# pfe-final.net
KiCad netlist of a schematic drawn in Altium Designer
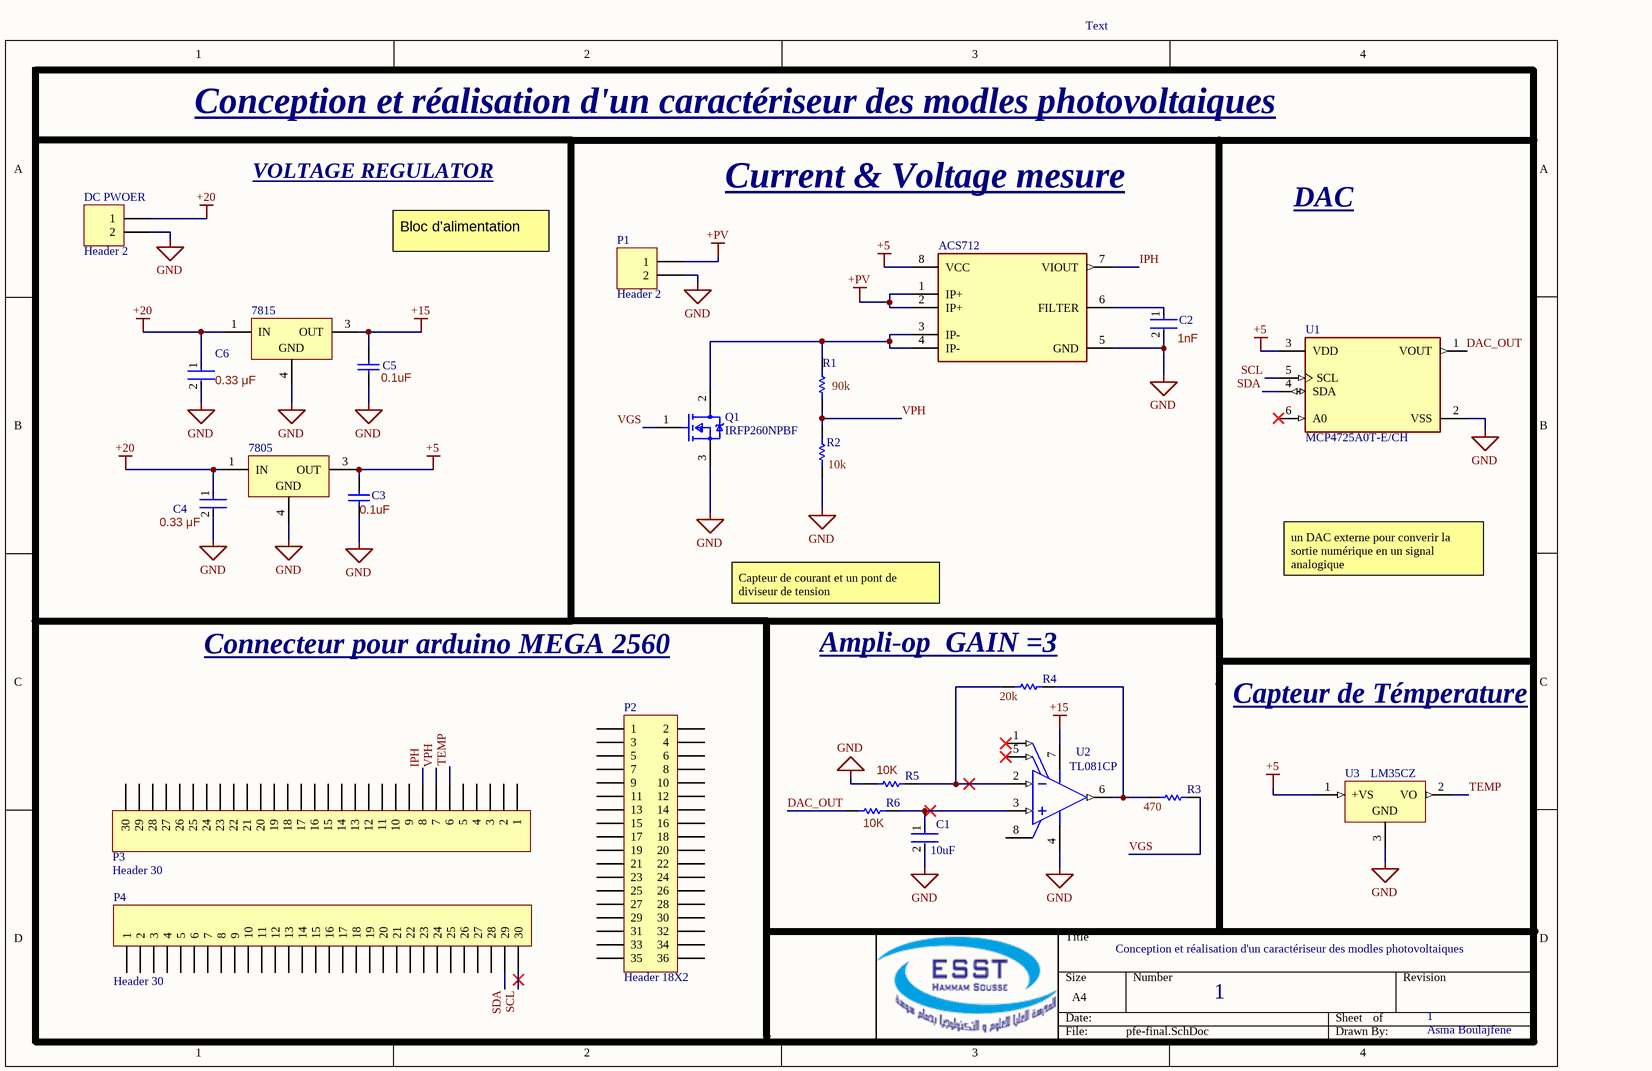
[diagram p0: pfe-final.SchDoc]

(export (version "E")
  (design (tool "Eeschema 10.0.6"))
  (components
    (comp (ref "7805")
      (value "L7805CD2T-TR")
      (footprint "TO-263_M")
      (description "Positive Voltage Regulator, 3-Pin D2PAK, Tape and Reel")
      (libsource (lib "Altium Content Vault") (part "PM-REG-L4940-SOT3"))
    )
    (comp (ref "7815")
      (value "L7815CD2T-TR")
      (footprint "TO-263_N")
      (description "Positive Voltage Regulator, 3-Pin D2PAK, Tape and Reel")
      (libsource (lib "Altium Content Vault") (part "PM-REG-L4940-SOT3"))
    )
    (comp (ref "ACS712")
      (value "ACS712ELCTR-30A-T")
      (footprint "FP-LC-8-IPC_C")
      (description "SENSOR CURRENT HALL 30A AC/DC")
      (libsource (lib "Altium Content Vault") (part "a0faa98973ef06dd62ff869f1199b2d"))
    )
    (comp (ref "C1")
      (value "10uF")
      (footprint "FP-C0805C-DG-MFG")
      (description "CAP CER 10UF 10V X5R 0805")
      (fields (field (name "TOLERANCE") "10%") (field (name "MANUFACTURER PART NUMBER") "C0805C106K8PACTU"))
      (libsource (lib "Altium Content Vault") (part "11868f565c42a9108669ba33697ecf6"))
    )
    (comp (ref "C2")
      (value "1nF")
      (footprint "FP-C0805C-DN-MFG")
      (description "CAP CER 1000PF 100V C0G/NP0 0805")
      (fields (field (name "MANUFACTURER") "KEMET") (field (name "TOLERANCE") "0.05"))
      (libsource (lib "Altium Content Vault") (part "b4654b650e69147ec39a6b967a45e02"))
    )
    (comp (ref "C3")
      (value "GRM21BR71H104KA01L")
      (footprint "CAPC2013X135X45ML10T25")
      (description "Chip Capacitor, 0.1 uF, +/- 10%, 50 V, -55 to 125 degC, 0805 (2012 Metric), RoHS, Tape and Reel")
      (fields
        (field (name "VOLTAGE") "50V")
        (field (name "CAPACITANCE") "0.1uF")
        (field (name "TOLERANCE") "10%")
      )
      (libsource (lib "Altium Content Vault") (part "CAP-NP-2"))
    )
    (comp (ref "C4")
      (value "0.33 μF")
      (footprint "FP-C0805C-DN-MFG")
      (description "CAP CER 0.33UF 50V X7R 0805")
      (fields
        (field (name "MANUFACTURER PART NUMBER") "C0805C334K5RACTU")
        (field (name "MANUFACTURER") "KEMET")
      )
      (libsource (lib "Altium Content Vault") (part "b4654b650e69147ec39a6b967a45e02"))
    )
    (comp (ref "C5")
      (value "GRM21BR71H104KA01L")
      (footprint "CAPC2013X135X45ML10T25")
      (description "Chip Capacitor, 0.1 uF, +/- 10%, 50 V, -55 to 125 degC, 0805 (2012 Metric), RoHS, Tape and Reel")
      (fields
        (field (name "VOLTAGE") "50V")
        (field (name "CAPACITANCE") "0.1uF")
        (field (name "TOLERANCE") "10%")
      )
      (libsource (lib "Altium Content Vault") (part "CAP-NP-2"))
    )
    (comp (ref "C6")
      (value "0.33 μF")
      (footprint "FP-C0805C-DN-MFG")
      (description "CAP CER 0.33UF 50V X7R 0805")
      (fields
        (field (name "MANUFACTURER PART NUMBER") "C0805C334K5RACTU")
        (field (name "MANUFACTURER") "KEMET")
      )
      (libsource (lib "Altium Content Vault") (part "b4654b650e69147ec39a6b967a45e02"))
    )
    (comp (ref "DC PWOER")
      (value "Header 2")
      (footprint "HDR1X2")
      (description "Header, 2-Pin")
      (fields (field (name "PUBLISHER") "Altium Limited"))
      (libsource (lib "Miscellaneous Connectors") (part "Header 2"))
    )
    (comp (ref "P1")
      (value "Header 2")
      (footprint "HDR1X2")
      (description "Header, 2-Pin")
      (fields (field (name "PUBLISHER") "Altium Limited"))
      (libsource (lib "Miscellaneous Connectors") (part "Header 2"))
    )
    (comp (ref "P2")
      (value "Header 18X2")
      (footprint "HDR2X18")
      (description "Header, 18-Pin, Dual row")
      (fields (field (name "PUBLISHER") "Altium Limited"))
      (libsource (lib "Miscellaneous Connectors") (part "Header 18X2"))
    )
    (comp (ref "P3")
      (value "Header 30")
      (footprint "HDR1X30")
      (description "Header, 30-Pin")
      (fields (field (name "PUBLISHER") "Altium Limited"))
      (libsource (lib "Miscellaneous Connectors") (part "Header 30"))
    )
    (comp (ref "P4")
      (value "Header 30")
      (footprint "HDR1X30")
      (description "Header, 30-Pin")
      (fields (field (name "PUBLISHER") "Altium Limited"))
      (libsource (lib "") (part "Header 30_1"))
    )
    (comp (ref "Q1")
      (value "IRFP260NPBF")
      (footprint "FP-PG-TO247-3-MFG")
      (description "MOSFET N-CH 200V 50A TO247AC")
      (libsource (lib "Altium Content Vault") (part "b09f7f152735e370c1ea22a33fa83d6"))
    )
    (comp (ref "R1")
      (value "90k")
      (footprint "RESC0805(2012)_M")
      (description "150K 0.125W 1% 0805 (2012 Metric)  SMD")
      (fields (field (name "TOLERANCE") "1 %") (field (name "POWER") "0.125 W"))
      (libsource (lib "Altium Content Vault") (part "RES"))
    )
    (comp (ref "R2")
      (value "10k")
      (footprint "RESC2013X60X35NL10T20")
      (description "Chip Resistor, 10 KOhm, +/- 1%, 0.125 W, -55 to 155 degC, 0805 (2012 Metric), RoHS, Tape and Reel")
      (fields (field (name "MANUFACTURER") "Yageo") (field (name "Comment") "RC0805FR-0710KL"))
      (libsource (lib "Altium Content Vault") (part "RES-2"))
    )
    (comp (ref "R3")
      (value "470")
      (footprint "RESC2013X60X35NL10T20")
      (description "Chip Resistor, 10 KOhm, +/- 1%, 0.125 W, -55 to 155 degC, 0805 (2012 Metric), RoHS, Tape and Reel")
      (fields (field (name "MANUFACTURER") "Yageo") (field (name "Comment") "RC0805FR-0710KL"))
      (libsource (lib "Altium Content Vault") (part "RES-2"))
    )
    (comp (ref "R4")
      (value "20k")
      (footprint "RESC2013X60X35NL10T20")
      (description "Chip Resistor, 10 KOhm, +/- 1%, 0.125 W, -55 to 155 degC, 0805 (2012 Metric), RoHS, Tape and Reel")
      (fields (field (name "MANUFACTURER") "Yageo") (field (name "Comment") "RC0805FR-0710KL"))
      (libsource (lib "Altium Content Vault") (part "RES-2"))
    )
    (comp (ref "R5")
      (value "10K")
      (footprint "RESC2013X60X35NL10T20")
      (description "Chip Resistor, 10 KOhm, +/- 1%, 0.125 W, -55 to 155 degC, 0805 (2012 Metric), RoHS, Tape and Reel")
      (fields (field (name "MANUFACTURER") "Yageo") (field (name "Comment") "RC0805FR-0710KL"))
      (libsource (lib "Altium Content Vault") (part "RES-2"))
    )
    (comp (ref "R6")
      (value "10K")
      (footprint "RESC2013X60X35NL10T20")
      (description "Chip Resistor, 10 KOhm, +/- 1%, 0.125 W, -55 to 155 degC, 0805 (2012 Metric), RoHS, Tape and Reel")
      (fields (field (name "MANUFACTURER") "Yageo") (field (name "Comment") "RC0805FR-0710KL"))
      (libsource (lib "Altium Content Vault") (part "RES-2"))
    )
    (comp (ref "U1")
      (value "MCP4725A0T-E/CH")
      (footprint "FP-C04-028-CHY-IPC_B")
      (description "IC DAC 12BIT V-OUT SOT23-6")
      (libsource (lib "Components - 16.06.25 - 13.24") (part "CMP-0188-00760-3"))
    )
    (comp (ref "U2")
      (value "TL081CP")
      (footprint "P0008A")
      (description "JFET-Input Operational Amplifier, 7 to 36 V, 0 to 70 degC, 8-pin DIP (P8), Pb-Free (RoHS)")
      (fields (field (name "MANUFACTURER") "Texas Instruments"))
      (libsource (lib "Altium Content Vault") (part "TI-AMP-S5-2-8"))
    )
    (comp (ref "U3")
      (value "LM35CZ")
      (footprint "Z03A")
      (description "Precision Centigrade Temperature Sensor, 3-pin TO-92")
      (fields (field (name "MANUFACTURER") "National Semiconductor"))
      (libsource (lib "Altium Content Vault") (part "SEN-TEMP-LM34AH-3"))
    )
  )
  (nets
    (net (code "1") (name "+5") (class "Default")
      (node (ref "7805") (pin "3") (pinfunction "OUT_3") (pintype "power_in"))
      (node (ref "ACS712") (pin "8") (pinfunction "VCC_8") (pintype "power_in"))
      (node (ref "C3") (pin "2") (pinfunction "2_2") (pintype "passive"))
      (node (ref "U1") (pin "3") (pinfunction "VDD_3") (pintype "power_in"))
      (node (ref "U3") (pin "1") (pinfunction "+VS_1") (pintype "input"))
    )
    (net (code "2") (name "+15") (class "Default")
      (node (ref "7815") (pin "3") (pinfunction "OUT_3") (pintype "power_in"))
      (node (ref "C5") (pin "2") (pinfunction "2_2") (pintype "passive"))
      (node (ref "U2") (pin "7") (pinfunction "VCC+_7") (pintype "power_in"))
    )
    (net (code "3") (name "+20") (class "Default")
      (node (ref "7805") (pin "1") (pinfunction "IN_1") (pintype "power_in"))
      (node (ref "7815") (pin "1") (pinfunction "IN_1") (pintype "power_in"))
      (node (ref "C4") (pin "1") (pinfunction "1_1") (pintype "passive"))
      (node (ref "C6") (pin "1") (pinfunction "1_1") (pintype "passive"))
      (node (ref "DC PWOER") (pin "1") (pinfunction "1_1") (pintype "passive"))
    )
    (net (code "4") (name "+PV") (class "Default")
      (node (ref "ACS712") (pin "1") (pinfunction "IP+_1") (pintype "passive"))
      (node (ref "ACS712") (pin "2") (pinfunction "IP+_2") (pintype "passive"))
      (node (ref "P1") (pin "1") (pinfunction "1_1") (pintype "passive"))
    )
    (net (code "5") (name "/DAC_OUT") (class "Default")
      (node (ref "R6") (pin "1") (pinfunction "1_1") (pintype "passive"))
      (node (ref "U1") (pin "1") (pinfunction "VOUT_1") (pintype "output"))
    )
    (net (code "6") (name "/IPH") (class "Default")
      (node (ref "ACS712") (pin "7") (pinfunction "VIOUT_7") (pintype "output"))
      (node (ref "P3") (pin "8") (pinfunction "8_8") (pintype "passive"))
    )
    (net (code "7") (name "/SCL") (class "Default")
      (node (ref "P4") (pin "30") (pinfunction "30_30") (pintype "passive"))
      (node (ref "U1") (pin "5") (pinfunction "SCL_5") (pintype "input"))
    )
    (net (code "8") (name "/SDA") (class "Default")
      (node (ref "P4") (pin "29") (pinfunction "29_29") (pintype "passive"))
      (node (ref "U1") (pin "4") (pinfunction "SDA_4") (pintype "bidirectional"))
    )
    (net (code "9") (name "/TEMP") (class "Default")
      (node (ref "P3") (pin "6") (pinfunction "6_6") (pintype "passive"))
      (node (ref "U3") (pin "2") (pinfunction "VO_2") (pintype "output"))
    )
    (net (code "10") (name "/VGS") (class "Default")
      (node (ref "Q1") (pin "1") (pinfunction "G_1") (pintype "passive"))
      (node (ref "R3") (pin "2") (pinfunction "2_2") (pintype "passive"))
    )
    (net (code "11") (name "/VPH") (class "Default")
      (node (ref "P3") (pin "7") (pinfunction "7_7") (pintype "passive"))
      (node (ref "R1") (pin "1") (pinfunction "1_1") (pintype "passive"))
      (node (ref "R2") (pin "2") (pinfunction "2_2") (pintype "passive"))
    )
    (net (code "12") (name "GND") (class "Default")
      (node (ref "7805") (pin "4") (pinfunction "GND_4") (pintype "power_in"))
      (node (ref "7815") (pin "4") (pinfunction "GND_4") (pintype "power_in"))
      (node (ref "ACS712") (pin "5") (pinfunction "GND_5") (pintype "power_in"))
      (node (ref "C1") (pin "2") (pinfunction "2_2") (pintype "passive"))
      (node (ref "C2") (pin "2") (pinfunction "2_2") (pintype "passive"))
      (node (ref "C3") (pin "1") (pinfunction "1_1") (pintype "passive"))
      (node (ref "C4") (pin "2") (pinfunction "2_2") (pintype "passive"))
      (node (ref "C5") (pin "1") (pinfunction "1_1") (pintype "passive"))
      (node (ref "C6") (pin "2") (pinfunction "2_2") (pintype "passive"))
      (node (ref "DC PWOER") (pin "2") (pinfunction "2_2") (pintype "passive"))
      (node (ref "P1") (pin "2") (pinfunction "2_2") (pintype "passive"))
      (node (ref "Q1") (pin "3") (pinfunction "S_3") (pintype "passive"))
      (node (ref "R2") (pin "1") (pinfunction "1_1") (pintype "passive"))
      (node (ref "R5") (pin "1") (pinfunction "1_1") (pintype "passive"))
      (node (ref "U1") (pin "2") (pinfunction "VSS_2") (pintype "power_in"))
      (node (ref "U2") (pin "4") (pinfunction "VCC-_4") (pintype "power_in"))
      (node (ref "U3") (pin "3") (pinfunction "GND_3") (pintype "power_in"))
    )
    (net (code "13") (name "Net-(ACS712-FILTER)") (class "Default")
      (node (ref "ACS712") (pin "6") (pinfunction "FILTER_6") (pintype "passive"))
      (node (ref "C2") (pin "1") (pinfunction "1_1") (pintype "passive"))
    )
    (net (code "14") (name "Net-(Q1-D)") (class "Default")
      (node (ref "ACS712") (pin "3") (pinfunction "IP-_3") (pintype "passive"))
      (node (ref "ACS712") (pin "4") (pinfunction "IP-_4") (pintype "passive"))
      (node (ref "Q1") (pin "2") (pinfunction "D_2") (pintype "passive"))
      (node (ref "R1") (pin "2") (pinfunction "2_2") (pintype "passive"))
    )
    (net (code "15") (name "Net-(U2-IN+)") (class "Default")
      (node (ref "C1") (pin "1") (pinfunction "1_1") (pintype "passive"))
      (node (ref "R6") (pin "2") (pinfunction "2_2") (pintype "passive"))
      (node (ref "U2") (pin "3") (pinfunction "IN+_3") (pintype "input"))
    )
    (net (code "16") (name "Net-(U2-IN-)") (class "Default")
      (node (ref "R4") (pin "1") (pinfunction "1_1") (pintype "passive"))
      (node (ref "R5") (pin "2") (pinfunction "2_2") (pintype "passive"))
      (node (ref "U2") (pin "2") (pinfunction "IN-_2") (pintype "input"))
    )
    (net (code "17") (name "Net-(U2-OUT)") (class "Default")
      (node (ref "R3") (pin "1") (pinfunction "1_1") (pintype "passive"))
      (node (ref "R4") (pin "2") (pinfunction "2_2") (pintype "passive"))
      (node (ref "U2") (pin "6") (pinfunction "OUT_6") (pintype "output"))
    )
    (net (code "18") (name "unconnected-(P2-Pad1)") (class "Default")
      (node (ref "P2") (pin "1") (pinfunction "1_1") (pintype "passive"))
    )
    (net (code "19") (name "unconnected-(P2-Pad2)") (class "Default")
      (node (ref "P2") (pin "2") (pinfunction "2_2") (pintype "passive"))
    )
    (net (code "20") (name "unconnected-(P2-Pad3)") (class "Default")
      (node (ref "P2") (pin "3") (pinfunction "3_3") (pintype "passive"))
    )
    (net (code "21") (name "unconnected-(P2-Pad4)") (class "Default")
      (node (ref "P2") (pin "4") (pinfunction "4_4") (pintype "passive"))
    )
    (net (code "22") (name "unconnected-(P2-Pad5)") (class "Default")
      (node (ref "P2") (pin "5") (pinfunction "5_5") (pintype "passive"))
    )
    (net (code "23") (name "unconnected-(P2-Pad6)") (class "Default")
      (node (ref "P2") (pin "6") (pinfunction "6_6") (pintype "passive"))
    )
    (net (code "24") (name "unconnected-(P2-Pad7)") (class "Default")
      (node (ref "P2") (pin "7") (pinfunction "7_7") (pintype "passive"))
    )
    (net (code "25") (name "unconnected-(P2-Pad8)") (class "Default")
      (node (ref "P2") (pin "8") (pinfunction "8_8") (pintype "passive"))
    )
    (net (code "26") (name "unconnected-(P2-Pad9)") (class "Default")
      (node (ref "P2") (pin "9") (pinfunction "9_9") (pintype "passive"))
    )
    (net (code "27") (name "unconnected-(P2-Pad10)") (class "Default")
      (node (ref "P2") (pin "10") (pinfunction "10_10") (pintype "passive"))
    )
    (net (code "28") (name "unconnected-(P2-Pad11)") (class "Default")
      (node (ref "P2") (pin "11") (pinfunction "11_11") (pintype "passive"))
    )
    (net (code "29") (name "unconnected-(P2-Pad12)") (class "Default")
      (node (ref "P2") (pin "12") (pinfunction "12_12") (pintype "passive"))
    )
    (net (code "30") (name "unconnected-(P2-Pad13)") (class "Default")
      (node (ref "P2") (pin "13") (pinfunction "13_13") (pintype "passive"))
    )
    (net (code "31") (name "unconnected-(P2-Pad14)") (class "Default")
      (node (ref "P2") (pin "14") (pinfunction "14_14") (pintype "passive"))
    )
    (net (code "32") (name "unconnected-(P2-Pad15)") (class "Default")
      (node (ref "P2") (pin "15") (pinfunction "15_15") (pintype "passive"))
    )
    (net (code "33") (name "unconnected-(P2-Pad16)") (class "Default")
      (node (ref "P2") (pin "16") (pinfunction "16_16") (pintype "passive"))
    )
    (net (code "34") (name "unconnected-(P2-Pad17)") (class "Default")
      (node (ref "P2") (pin "17") (pinfunction "17_17") (pintype "passive"))
    )
    (net (code "35") (name "unconnected-(P2-Pad18)") (class "Default")
      (node (ref "P2") (pin "18") (pinfunction "18_18") (pintype "passive"))
    )
    (net (code "36") (name "unconnected-(P2-Pad19)") (class "Default")
      (node (ref "P2") (pin "19") (pinfunction "19_19") (pintype "passive"))
    )
    (net (code "37") (name "unconnected-(P2-Pad20)") (class "Default")
      (node (ref "P2") (pin "20") (pinfunction "20_20") (pintype "passive"))
    )
    (net (code "38") (name "unconnected-(P2-Pad21)") (class "Default")
      (node (ref "P2") (pin "21") (pinfunction "21_21") (pintype "passive"))
    )
    (net (code "39") (name "unconnected-(P2-Pad22)") (class "Default")
      (node (ref "P2") (pin "22") (pinfunction "22_22") (pintype "passive"))
    )
    (net (code "40") (name "unconnected-(P2-Pad23)") (class "Default")
      (node (ref "P2") (pin "23") (pinfunction "23_23") (pintype "passive"))
    )
    (net (code "41") (name "unconnected-(P2-Pad24)") (class "Default")
      (node (ref "P2") (pin "24") (pinfunction "24_24") (pintype "passive"))
    )
    (net (code "42") (name "unconnected-(P2-Pad25)") (class "Default")
      (node (ref "P2") (pin "25") (pinfunction "25_25") (pintype "passive"))
    )
    (net (code "43") (name "unconnected-(P2-Pad26)") (class "Default")
      (node (ref "P2") (pin "26") (pinfunction "26_26") (pintype "passive"))
    )
    (net (code "44") (name "unconnected-(P2-Pad27)") (class "Default")
      (node (ref "P2") (pin "27") (pinfunction "27_27") (pintype "passive"))
    )
    (net (code "45") (name "unconnected-(P2-Pad28)") (class "Default")
      (node (ref "P2") (pin "28") (pinfunction "28_28") (pintype "passive"))
    )
    (net (code "46") (name "unconnected-(P2-Pad29)") (class "Default")
      (node (ref "P2") (pin "29") (pinfunction "29_29") (pintype "passive"))
    )
    (net (code "47") (name "unconnected-(P2-Pad30)") (class "Default")
      (node (ref "P2") (pin "30") (pinfunction "30_30") (pintype "passive"))
    )
    (net (code "48") (name "unconnected-(P2-Pad31)") (class "Default")
      (node (ref "P2") (pin "31") (pinfunction "31_31") (pintype "passive"))
    )
    (net (code "49") (name "unconnected-(P2-Pad32)") (class "Default")
      (node (ref "P2") (pin "32") (pinfunction "32_32") (pintype "passive"))
    )
    (net (code "50") (name "unconnected-(P2-Pad33)") (class "Default")
      (node (ref "P2") (pin "33") (pinfunction "33_33") (pintype "passive"))
    )
    (net (code "51") (name "unconnected-(P2-Pad34)") (class "Default")
      (node (ref "P2") (pin "34") (pinfunction "34_34") (pintype "passive"))
    )
    (net (code "52") (name "unconnected-(P2-Pad35)") (class "Default")
      (node (ref "P2") (pin "35") (pinfunction "35_35") (pintype "passive"))
    )
    (net (code "53") (name "unconnected-(P2-Pad36)") (class "Default")
      (node (ref "P2") (pin "36") (pinfunction "36_36") (pintype "passive"))
    )
    (net (code "54") (name "unconnected-(P3-Pad1)") (class "Default")
      (node (ref "P3") (pin "1") (pinfunction "1_1") (pintype "passive"))
    )
    (net (code "55") (name "unconnected-(P3-Pad2)") (class "Default")
      (node (ref "P3") (pin "2") (pinfunction "2_2") (pintype "passive"))
    )
    (net (code "56") (name "unconnected-(P3-Pad3)") (class "Default")
      (node (ref "P3") (pin "3") (pinfunction "3_3") (pintype "passive"))
    )
    (net (code "57") (name "unconnected-(P3-Pad4)") (class "Default")
      (node (ref "P3") (pin "4") (pinfunction "4_4") (pintype "passive"))
    )
    (net (code "58") (name "unconnected-(P3-Pad5)") (class "Default")
      (node (ref "P3") (pin "5") (pinfunction "5_5") (pintype "passive"))
    )
    (net (code "59") (name "unconnected-(P3-Pad9)") (class "Default")
      (node (ref "P3") (pin "9") (pinfunction "9_9") (pintype "passive"))
    )
    (net (code "60") (name "unconnected-(P3-Pad10)") (class "Default")
      (node (ref "P3") (pin "10") (pinfunction "10_10") (pintype "passive"))
    )
    (net (code "61") (name "unconnected-(P3-Pad11)") (class "Default")
      (node (ref "P3") (pin "11") (pinfunction "11_11") (pintype "passive"))
    )
    (net (code "62") (name "unconnected-(P3-Pad12)") (class "Default")
      (node (ref "P3") (pin "12") (pinfunction "12_12") (pintype "passive"))
    )
    (net (code "63") (name "unconnected-(P3-Pad13)") (class "Default")
      (node (ref "P3") (pin "13") (pinfunction "13_13") (pintype "passive"))
    )
    (net (code "64") (name "unconnected-(P3-Pad14)") (class "Default")
      (node (ref "P3") (pin "14") (pinfunction "14_14") (pintype "passive"))
    )
    (net (code "65") (name "unconnected-(P3-Pad15)") (class "Default")
      (node (ref "P3") (pin "15") (pinfunction "15_15") (pintype "passive"))
    )
    (net (code "66") (name "unconnected-(P3-Pad16)") (class "Default")
      (node (ref "P3") (pin "16") (pinfunction "16_16") (pintype "passive"))
    )
    (net (code "67") (name "unconnected-(P3-Pad17)") (class "Default")
      (node (ref "P3") (pin "17") (pinfunction "17_17") (pintype "passive"))
    )
    (net (code "68") (name "unconnected-(P3-Pad18)") (class "Default")
      (node (ref "P3") (pin "18") (pinfunction "18_18") (pintype "passive"))
    )
    (net (code "69") (name "unconnected-(P3-Pad19)") (class "Default")
      (node (ref "P3") (pin "19") (pinfunction "19_19") (pintype "passive"))
    )
    (net (code "70") (name "unconnected-(P3-Pad20)") (class "Default")
      (node (ref "P3") (pin "20") (pinfunction "20_20") (pintype "passive"))
    )
    (net (code "71") (name "unconnected-(P3-Pad21)") (class "Default")
      (node (ref "P3") (pin "21") (pinfunction "21_21") (pintype "passive"))
    )
    (net (code "72") (name "unconnected-(P3-Pad22)") (class "Default")
      (node (ref "P3") (pin "22") (pinfunction "22_22") (pintype "passive"))
    )
    (net (code "73") (name "unconnected-(P3-Pad23)") (class "Default")
      (node (ref "P3") (pin "23") (pinfunction "23_23") (pintype "passive"))
    )
    (net (code "74") (name "unconnected-(P3-Pad24)") (class "Default")
      (node (ref "P3") (pin "24") (pinfunction "24_24") (pintype "passive"))
    )
    (net (code "75") (name "unconnected-(P3-Pad25)") (class "Default")
      (node (ref "P3") (pin "25") (pinfunction "25_25") (pintype "passive"))
    )
    (net (code "76") (name "unconnected-(P3-Pad26)") (class "Default")
      (node (ref "P3") (pin "26") (pinfunction "26_26") (pintype "passive"))
    )
    (net (code "77") (name "unconnected-(P3-Pad27)") (class "Default")
      (node (ref "P3") (pin "27") (pinfunction "27_27") (pintype "passive"))
    )
    (net (code "78") (name "unconnected-(P3-Pad28)") (class "Default")
      (node (ref "P3") (pin "28") (pinfunction "28_28") (pintype "passive"))
    )
    (net (code "79") (name "unconnected-(P3-Pad29)") (class "Default")
      (node (ref "P3") (pin "29") (pinfunction "29_29") (pintype "passive"))
    )
    (net (code "80") (name "unconnected-(P3-Pad30)") (class "Default")
      (node (ref "P3") (pin "30") (pinfunction "30_30") (pintype "passive"))
    )
    (net (code "81") (name "unconnected-(P4-Pad1)") (class "Default")
      (node (ref "P4") (pin "1") (pinfunction "1_1") (pintype "passive"))
    )
    (net (code "82") (name "unconnected-(P4-Pad2)") (class "Default")
      (node (ref "P4") (pin "2") (pinfunction "2_2") (pintype "passive"))
    )
    (net (code "83") (name "unconnected-(P4-Pad3)") (class "Default")
      (node (ref "P4") (pin "3") (pinfunction "3_3") (pintype "passive"))
    )
    (net (code "84") (name "unconnected-(P4-Pad4)") (class "Default")
      (node (ref "P4") (pin "4") (pinfunction "4_4") (pintype "passive"))
    )
    (net (code "85") (name "unconnected-(P4-Pad5)") (class "Default")
      (node (ref "P4") (pin "5") (pinfunction "5_5") (pintype "passive"))
    )
    (net (code "86") (name "unconnected-(P4-Pad6)") (class "Default")
      (node (ref "P4") (pin "6") (pinfunction "6_6") (pintype "passive"))
    )
    (net (code "87") (name "unconnected-(P4-Pad7)") (class "Default")
      (node (ref "P4") (pin "7") (pinfunction "7_7") (pintype "passive"))
    )
    (net (code "88") (name "unconnected-(P4-Pad8)") (class "Default")
      (node (ref "P4") (pin "8") (pinfunction "8_8") (pintype "passive"))
    )
    (net (code "89") (name "unconnected-(P4-Pad9)") (class "Default")
      (node (ref "P4") (pin "9") (pinfunction "9_9") (pintype "passive"))
    )
    (net (code "90") (name "unconnected-(P4-Pad10)") (class "Default")
      (node (ref "P4") (pin "10") (pinfunction "10_10") (pintype "passive"))
    )
    (net (code "91") (name "unconnected-(P4-Pad11)") (class "Default")
      (node (ref "P4") (pin "11") (pinfunction "11_11") (pintype "passive"))
    )
    (net (code "92") (name "unconnected-(P4-Pad12)") (class "Default")
      (node (ref "P4") (pin "12") (pinfunction "12_12") (pintype "passive"))
    )
    (net (code "93") (name "unconnected-(P4-Pad13)") (class "Default")
      (node (ref "P4") (pin "13") (pinfunction "13_13") (pintype "passive"))
    )
    (net (code "94") (name "unconnected-(P4-Pad14)") (class "Default")
      (node (ref "P4") (pin "14") (pinfunction "14_14") (pintype "passive"))
    )
    (net (code "95") (name "unconnected-(P4-Pad15)") (class "Default")
      (node (ref "P4") (pin "15") (pinfunction "15_15") (pintype "passive"))
    )
    (net (code "96") (name "unconnected-(P4-Pad16)") (class "Default")
      (node (ref "P4") (pin "16") (pinfunction "16_16") (pintype "passive"))
    )
    (net (code "97") (name "unconnected-(P4-Pad17)") (class "Default")
      (node (ref "P4") (pin "17") (pinfunction "17_17") (pintype "passive"))
    )
    (net (code "98") (name "unconnected-(P4-Pad18)") (class "Default")
      (node (ref "P4") (pin "18") (pinfunction "18_18") (pintype "passive"))
    )
    (net (code "99") (name "unconnected-(P4-Pad19)") (class "Default")
      (node (ref "P4") (pin "19") (pinfunction "19_19") (pintype "passive"))
    )
    (net (code "100") (name "unconnected-(P4-Pad20)") (class "Default")
      (node (ref "P4") (pin "20") (pinfunction "20_20") (pintype "passive"))
    )
    (net (code "101") (name "unconnected-(P4-Pad21)") (class "Default")
      (node (ref "P4") (pin "21") (pinfunction "21_21") (pintype "passive"))
    )
    (net (code "102") (name "unconnected-(P4-Pad22)") (class "Default")
      (node (ref "P4") (pin "22") (pinfunction "22_22") (pintype "passive"))
    )
    (net (code "103") (name "unconnected-(P4-Pad23)") (class "Default")
      (node (ref "P4") (pin "23") (pinfunction "23_23") (pintype "passive"))
    )
    (net (code "104") (name "unconnected-(P4-Pad24)") (class "Default")
      (node (ref "P4") (pin "24") (pinfunction "24_24") (pintype "passive"))
    )
    (net (code "105") (name "unconnected-(P4-Pad25)") (class "Default")
      (node (ref "P4") (pin "25") (pinfunction "25_25") (pintype "passive"))
    )
    (net (code "106") (name "unconnected-(P4-Pad26)") (class "Default")
      (node (ref "P4") (pin "26") (pinfunction "26_26") (pintype "passive"))
    )
    (net (code "107") (name "unconnected-(P4-Pad27)") (class "Default")
      (node (ref "P4") (pin "27") (pinfunction "27_27") (pintype "passive"))
    )
    (net (code "108") (name "unconnected-(P4-Pad28)") (class "Default")
      (node (ref "P4") (pin "28") (pinfunction "28_28") (pintype "passive"))
    )
    (net (code "109") (name "unconnected-(U1-A0-Pad6)") (class "Default")
      (node (ref "U1") (pin "6") (pinfunction "A0_6") (pintype "input+no_connect"))
    )
    (net (code "110") (name "unconnected-(U2-NC-Pad8)") (class "Default")
      (node (ref "U2") (pin "8") (pinfunction "NC_8") (pintype "passive"))
    )
    (net (code "111") (name "unconnected-(U2-OFFSET_N1-Pad1)") (class "Default")
      (node (ref "U2") (pin "1") (pinfunction "OFFSET_N1_1") (pintype "input+no_connect"))
    )
    (net (code "112") (name "unconnected-(U2-OFFSET_N2-Pad5)") (class "Default")
      (node (ref "U2") (pin "5") (pinfunction "OFFSET_N2_5") (pintype "input+no_connect"))
    )
  )
)
